# -Z_axis_for_open_source.net
KiCad netlist of a schematic drawn in EAGLE
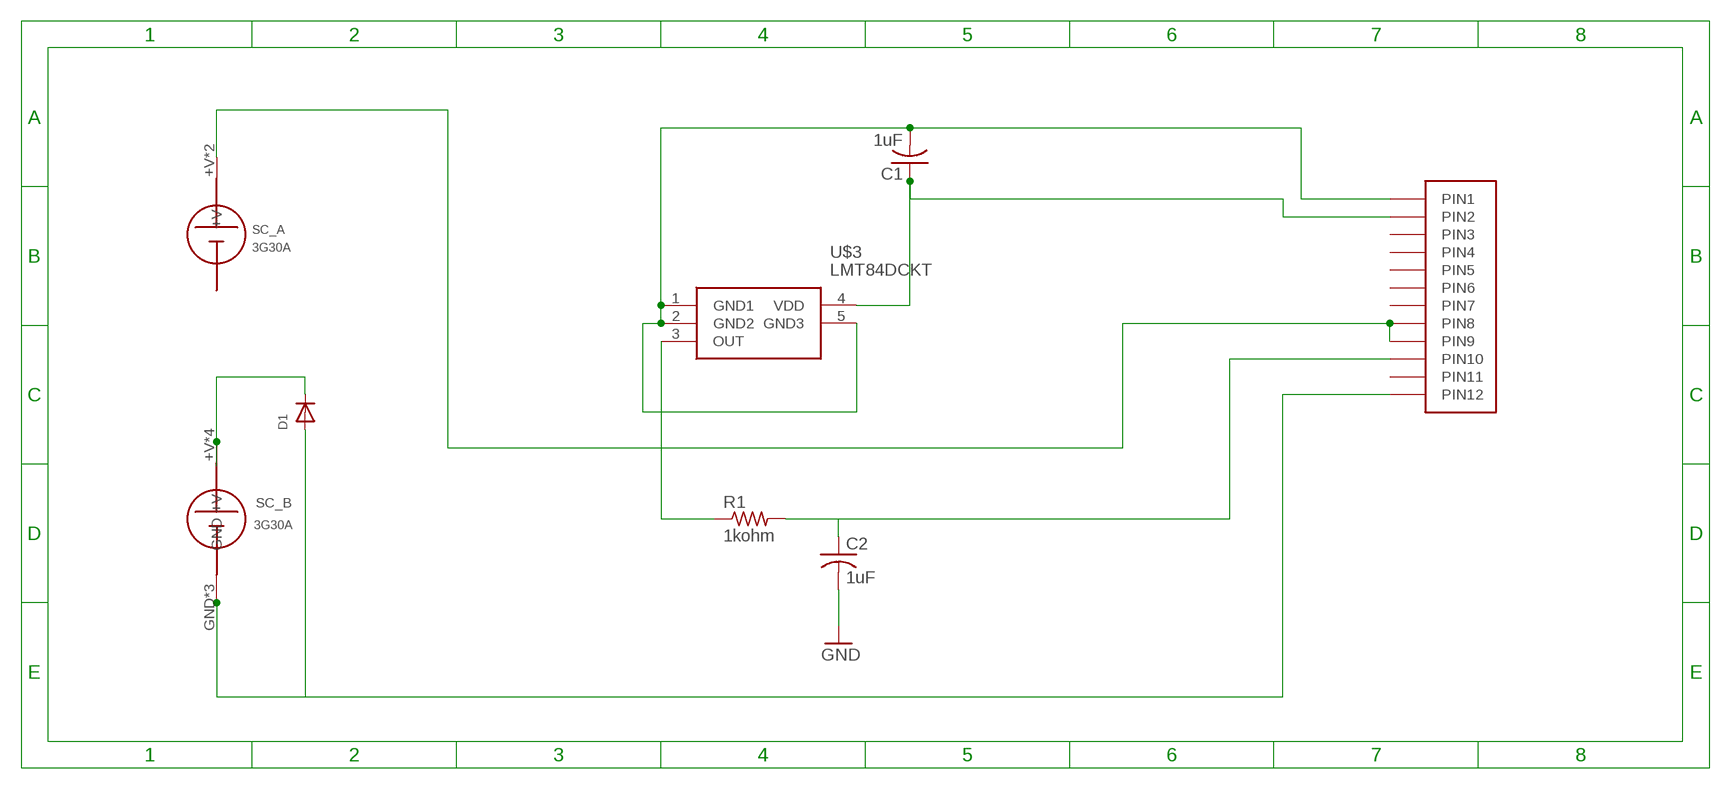
[diagram p0: schematic, sheet 1]

(export (version "E")
  (design (tool "Eeschema 10.0.6"))
  (components
    (comp (ref "C1")
      (value "1uF")
      (footprint "eagle-import:C0805")
      (libsource (lib "eagle-import") (part "C-USC0805"))
    )
    (comp (ref "C2")
      (value "1uF")
      (footprint "eagle-import:C0805")
      (libsource (lib "eagle-import") (part "C-USC0805"))
    )
    (comp (ref "D1")
      (value "DIODE_SOD-123FL")
      (footprint "eagle-import:SOD-123FL")
      (libsource (lib "eagle-import") (part "DIODE_SOD-123FL"))
    )
    (comp (ref "R1")
      (value "1kohm")
      (footprint "eagle-import:R0402")
      (libsource (lib "eagle-import") (part "R-US_R0402"))
    )
    (comp (ref "U$1")
      (value "HEADER12PIN")
      (footprint "eagle-import:HEADER12PIN")
      (libsource (lib "eagle-import") (part "HEADER12PIN"))
    )
    (comp (ref "U$3")
      (value "LMT84DCKT")
      (footprint "eagle-import:SOT65P210X110-5N")
      (fields (field (name "RS_PART_NUMBER") "8115860"))
      (libsource (lib "eagle-import") (part "LMT84DCKT"))
    )
    (comp (ref "U$4")
      (value "SC_A")
      (footprint "eagle-import:SC_A")
      (libsource (lib "eagle-import") (part "SC_A"))
    )
    (comp (ref "U$5")
      (value "SC_B")
      (footprint "eagle-import:SC_B")
      (libsource (lib "eagle-import") (part "SC_B"))
    )
  )
  (nets
    (net (code "1") (name "GND") (class "Default")
      (node (ref "C1") (pin "2") (pinfunction "2_2") (pintype "passive"))
      (node (ref "C2") (pin "2") (pinfunction "2_2") (pintype "passive"))
      (node (ref "D1") (pin "A") (pinfunction "A_A") (pintype "passive"))
      (node (ref "U$1") (pin "P1") (pinfunction "PIN1_P1") (pintype "bidirectional"))
      (node (ref "U$1") (pin "P12") (pinfunction "PIN12_P12") (pintype "bidirectional"))
      (node (ref "U$3") (pin "1") (pinfunction "GND1_1") (pintype "power_in"))
      (node (ref "U$3") (pin "2") (pinfunction "GND2_2") (pintype "power_in"))
      (node (ref "U$3") (pin "5") (pinfunction "GND3_5") (pintype "power_in"))
      (node (ref "U$5") (pin "GND") (pinfunction "GND_GND") (pintype "bidirectional"))
      (node (ref "U$5") (pin "GND1") (pinfunction "GND_GND1") (pintype "bidirectional"))
      (node (ref "U$5") (pin "GND2") (pinfunction "GND_GND2") (pintype "bidirectional"))
    )
    (net (code "2") (name "Net-(D1-PadC)") (class "Default")
      (node (ref "D1") (pin "C") (pinfunction "C_C") (pintype "passive"))
      (node (ref "U$5") (pin "+V") (pinfunction "+V_+V") (pintype "bidirectional"))
      (node (ref "U$5") (pin "+V2") (pinfunction "+V_+V2") (pintype "bidirectional"))
      (node (ref "U$5") (pin "+V3") (pinfunction "+V_+V3") (pintype "bidirectional"))
      (node (ref "U$5") (pin "+V4") (pinfunction "+V_+V4") (pintype "bidirectional"))
    )
    (net (code "3") (name "Net-(U$1-PIN2)") (class "Default")
      (node (ref "C1") (pin "1") (pinfunction "1_1") (pintype "passive"))
      (node (ref "U$1") (pin "P2") (pinfunction "PIN2_P2") (pintype "bidirectional"))
      (node (ref "U$3") (pin "4") (pinfunction "VDD_4") (pintype "power_in"))
    )
    (net (code "4") (name "Net-(U$1-PIN8)") (class "Default")
      (node (ref "U$1") (pin "P8") (pinfunction "PIN8_P8") (pintype "bidirectional"))
      (node (ref "U$1") (pin "P9") (pinfunction "PIN9_P9") (pintype "bidirectional"))
      (node (ref "U$4") (pin "+V") (pinfunction "+V_+V") (pintype "bidirectional"))
      (node (ref "U$4") (pin "+V1") (pinfunction "+V_+V1") (pintype "bidirectional"))
    )
    (net (code "5") (name "Net-(U$1-PIN10)") (class "Default")
      (node (ref "C2") (pin "1") (pinfunction "1_1") (pintype "passive"))
      (node (ref "R1") (pin "2") (pinfunction "2_2") (pintype "passive"))
      (node (ref "U$1") (pin "P10") (pinfunction "PIN10_P10") (pintype "bidirectional"))
    )
    (net (code "6") (name "Net-(U$3-OUT)") (class "Default")
      (node (ref "R1") (pin "1") (pinfunction "1_1") (pintype "passive"))
      (node (ref "U$3") (pin "3") (pinfunction "OUT_3") (pintype "output"))
    )
    (net (code "7") (name "unconnected-(U$1-PIN3-PadP3)") (class "Default")
      (node (ref "U$1") (pin "P3") (pinfunction "PIN3_P3") (pintype "bidirectional"))
    )
    (net (code "8") (name "unconnected-(U$1-PIN4-PadP4)") (class "Default")
      (node (ref "U$1") (pin "P4") (pinfunction "PIN4_P4") (pintype "bidirectional"))
    )
    (net (code "9") (name "unconnected-(U$1-PIN5-PadP5)") (class "Default")
      (node (ref "U$1") (pin "P5") (pinfunction "PIN5_P5") (pintype "bidirectional"))
    )
    (net (code "10") (name "unconnected-(U$1-PIN6-PadP6)") (class "Default")
      (node (ref "U$1") (pin "P6") (pinfunction "PIN6_P6") (pintype "bidirectional"))
    )
    (net (code "11") (name "unconnected-(U$1-PIN7-PadP7)") (class "Default")
      (node (ref "U$1") (pin "P7") (pinfunction "PIN7_P7") (pintype "bidirectional"))
    )
    (net (code "12") (name "unconnected-(U$1-PIN11-PadP11)") (class "Default")
      (node (ref "U$1") (pin "P11") (pinfunction "PIN11_P11") (pintype "bidirectional"))
    )
  )
)
